# connector.net
KiCad netlist of a schematic drawn in Altium Designer
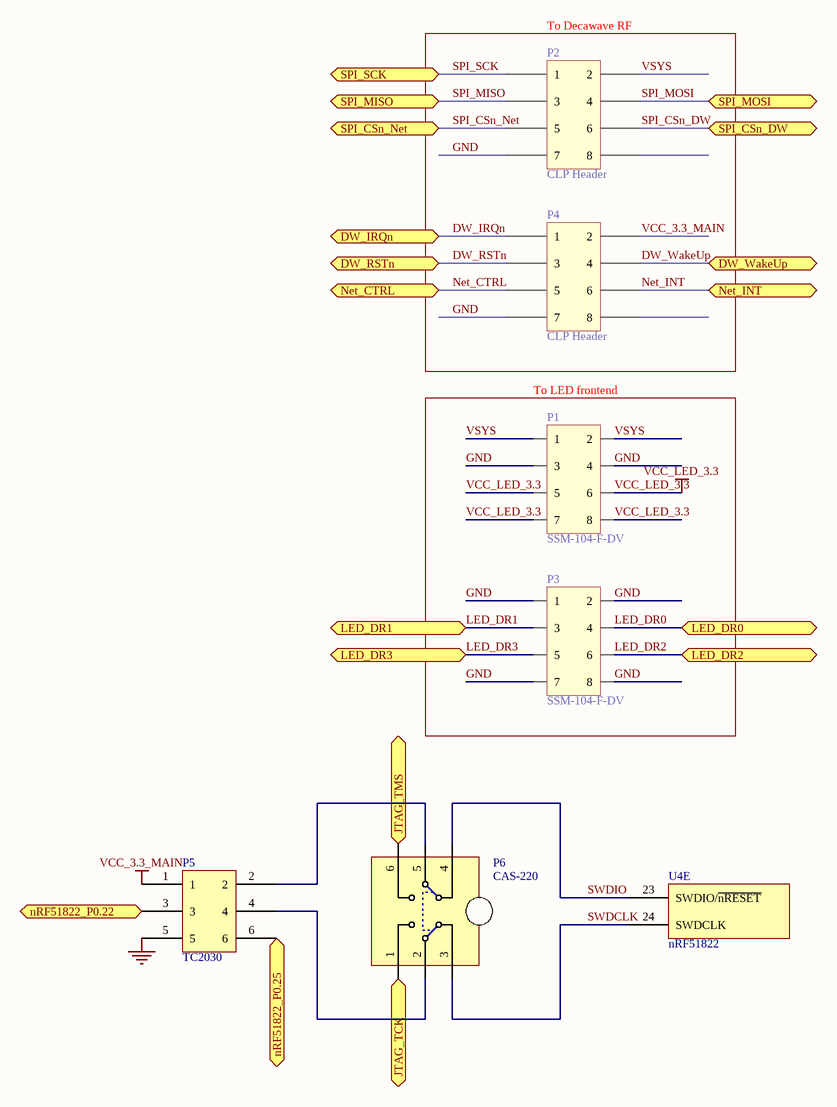
[diagram p0: connector.SchDoc]

(export (version "E")
  (design (tool "Eeschema 10.0.6"))
  (components
    (comp (ref "P1")
      (value "SSM-104-F-DV")
      (footprint "SSM-104-F-DV")
      (description "Samtec 2x4 100 mil female connector")
      (libsource (lib "connectors") (part "SSM-104-F-DV"))
    )
    (comp (ref "P2")
      (value "CLP Header")
      (footprint "SAM_CLP_2_4")
      (description "Samtec CLP 2x4 0.05\" Female Header")
      (libsource (lib "connectors") (part "CLP Header"))
    )
    (comp (ref "P3")
      (value "SSM-104-F-DV")
      (footprint "SSM-104-F-DV")
      (description "Samtec 2x4 100 mil female connector")
      (libsource (lib "connectors") (part "SSM-104-F-DV"))
    )
    (comp (ref "P4")
      (value "CLP Header")
      (footprint "SAM_CLP_2_4")
      (description "Samtec CLP 2x4 0.05\" Female Header")
      (libsource (lib "connectors") (part "CLP Header"))
    )
    (comp (ref "P5")
      (value "TC2030")
      (footprint "TC2030-IDC-NLFP")
      (description "TC2030-MCP-NL")
      (libsource (lib "connectors") (part "TC2030"))
    )
    (comp (ref "P6")
      (value "CAS-220")
      (footprint "CAS-220A")
      (description "DPDT dip switch")
      (libsource (lib "connectors") (part "CAS-220"))
    )
    (comp (ref "U4")
      (value "nRF51822")
      (footprint "QFN-48")
      (description "Multiprotocol Bluetooth® low energy/2.4 GHz RF System on Chip")
      (libsource (lib "sdl") (part "nRF51822"))
    )
  )
  (nets
    (net (code "1") (name "/DW_IRQn") (class "Default")
      (node (ref "P4") (pin "1") (pinfunction "1_1") (pintype "passive"))
    )
    (net (code "2") (name "/DW_RSTn") (class "Default")
      (node (ref "P4") (pin "3") (pinfunction "3_3") (pintype "passive"))
    )
    (net (code "3") (name "/DW_WakeUp") (class "Default")
      (node (ref "P4") (pin "4") (pinfunction "4_4") (pintype "passive"))
    )
    (net (code "4") (name "/JTAG_TCK") (class "Default")
      (node (ref "P6") (pin "1") (pinfunction "1_1") (pintype "passive"))
    )
    (net (code "5") (name "/JTAG_TMS") (class "Default")
      (node (ref "P6") (pin "6") (pinfunction "6_6") (pintype "passive"))
    )
    (net (code "6") (name "/LED_DR0") (class "Default")
      (node (ref "P3") (pin "4") (pinfunction "4_4") (pintype "power_in"))
    )
    (net (code "7") (name "/LED_DR1") (class "Default")
      (node (ref "P3") (pin "3") (pinfunction "3_3") (pintype "passive"))
    )
    (net (code "8") (name "/LED_DR2") (class "Default")
      (node (ref "P3") (pin "6") (pinfunction "6_6") (pintype "power_in"))
    )
    (net (code "9") (name "/LED_DR3") (class "Default")
      (node (ref "P3") (pin "5") (pinfunction "5_5") (pintype "power_in"))
    )
    (net (code "10") (name "/Net_CTRL") (class "Default")
      (node (ref "P4") (pin "5") (pinfunction "5_5") (pintype "passive"))
    )
    (net (code "11") (name "/Net_INT") (class "Default")
      (node (ref "P4") (pin "6") (pinfunction "6_6") (pintype "passive"))
    )
    (net (code "12") (name "/SPI_CSn_DW") (class "Default")
      (node (ref "P2") (pin "6") (pinfunction "6_6") (pintype "passive"))
    )
    (net (code "13") (name "/SPI_CSn_Net") (class "Default")
      (node (ref "P2") (pin "5") (pinfunction "5_5") (pintype "passive"))
    )
    (net (code "14") (name "/SPI_MISO") (class "Default")
      (node (ref "P2") (pin "3") (pinfunction "3_3") (pintype "passive"))
    )
    (net (code "15") (name "/SPI_MOSI") (class "Default")
      (node (ref "P2") (pin "4") (pinfunction "4_4") (pintype "passive"))
    )
    (net (code "16") (name "/SPI_SCK") (class "Default")
      (node (ref "P2") (pin "1") (pinfunction "1_1") (pintype "passive"))
    )
    (net (code "17") (name "/SWDCLK") (class "Default")
      (node (ref "P6") (pin "3") (pinfunction "3_3") (pintype "passive"))
      (node (ref "U4") (pin "24") (pinfunction "SWDCLK_24") (pintype "passive"))
    )
    (net (code "18") (name "/SWDIO") (class "Default")
      (node (ref "P6") (pin "4") (pinfunction "4_4") (pintype "passive"))
      (node (ref "U4") (pin "23") (pinfunction "SWDIO/~{nRESET}_23") (pintype "passive"))
    )
    (net (code "19") (name "/VSYS") (class "Default")
      (node (ref "P1") (pin "1") (pinfunction "1_1") (pintype "passive"))
      (node (ref "P1") (pin "2") (pinfunction "2_2") (pintype "passive"))
      (node (ref "P2") (pin "2") (pinfunction "2_2") (pintype "passive"))
    )
    (net (code "20") (name "/nRF51822_P0.22") (class "Default")
      (node (ref "P5") (pin "3") (pinfunction "3_3") (pintype "passive"))
    )
    (net (code "21") (name "/nRF51822_P0.25") (class "Default")
      (node (ref "P5") (pin "6") (pinfunction "6_6") (pintype "passive"))
    )
    (net (code "22") (name "GND") (class "Default")
      (node (ref "P1") (pin "3") (pinfunction "3_3") (pintype "passive"))
      (node (ref "P1") (pin "4") (pinfunction "4_4") (pintype "power_in"))
      (node (ref "P2") (pin "7") (pinfunction "7_7") (pintype "passive"))
      (node (ref "P3") (pin "1") (pinfunction "1_1") (pintype "passive"))
      (node (ref "P3") (pin "2") (pinfunction "2_2") (pintype "passive"))
      (node (ref "P3") (pin "7") (pinfunction "7_7") (pintype "power_in"))
      (node (ref "P3") (pin "8") (pinfunction "8_8") (pintype "power_in"))
      (node (ref "P4") (pin "7") (pinfunction "7_7") (pintype "passive"))
      (node (ref "P5") (pin "5") (pinfunction "5_5") (pintype "passive"))
    )
    (net (code "23") (name "Net-(P5-Pad2)") (class "Default")
      (node (ref "P5") (pin "2") (pinfunction "2_2") (pintype "passive"))
      (node (ref "P6") (pin "5") (pinfunction "5_5") (pintype "passive"))
    )
    (net (code "24") (name "Net-(P5-Pad4)") (class "Default")
      (node (ref "P5") (pin "4") (pinfunction "4_4") (pintype "passive"))
      (node (ref "P6") (pin "2") (pinfunction "2_2") (pintype "passive"))
    )
    (net (code "25") (name "VCC_3.3_MAIN") (class "Default")
      (node (ref "P4") (pin "2") (pinfunction "2_2") (pintype "passive"))
      (node (ref "P5") (pin "1") (pinfunction "1_1") (pintype "passive"))
    )
    (net (code "26") (name "VCC_LED_3.3") (class "Default")
      (node (ref "P1") (pin "5") (pinfunction "5_5") (pintype "power_in"))
      (node (ref "P1") (pin "6") (pinfunction "6_6") (pintype "power_in"))
      (node (ref "P1") (pin "7") (pinfunction "7_7") (pintype "power_in"))
      (node (ref "P1") (pin "8") (pinfunction "8_8") (pintype "power_in"))
    )
    (net (code "27") (name "unconnected-(P2-Pad8)") (class "Default")
      (node (ref "P2") (pin "8") (pinfunction "8_8") (pintype "passive"))
    )
    (net (code "28") (name "unconnected-(P4-Pad8)") (class "Default")
      (node (ref "P4") (pin "8") (pinfunction "8_8") (pintype "passive"))
    )
  )
)
